# combo.net
KiCad netlist of a schematic drawn in EAGLE
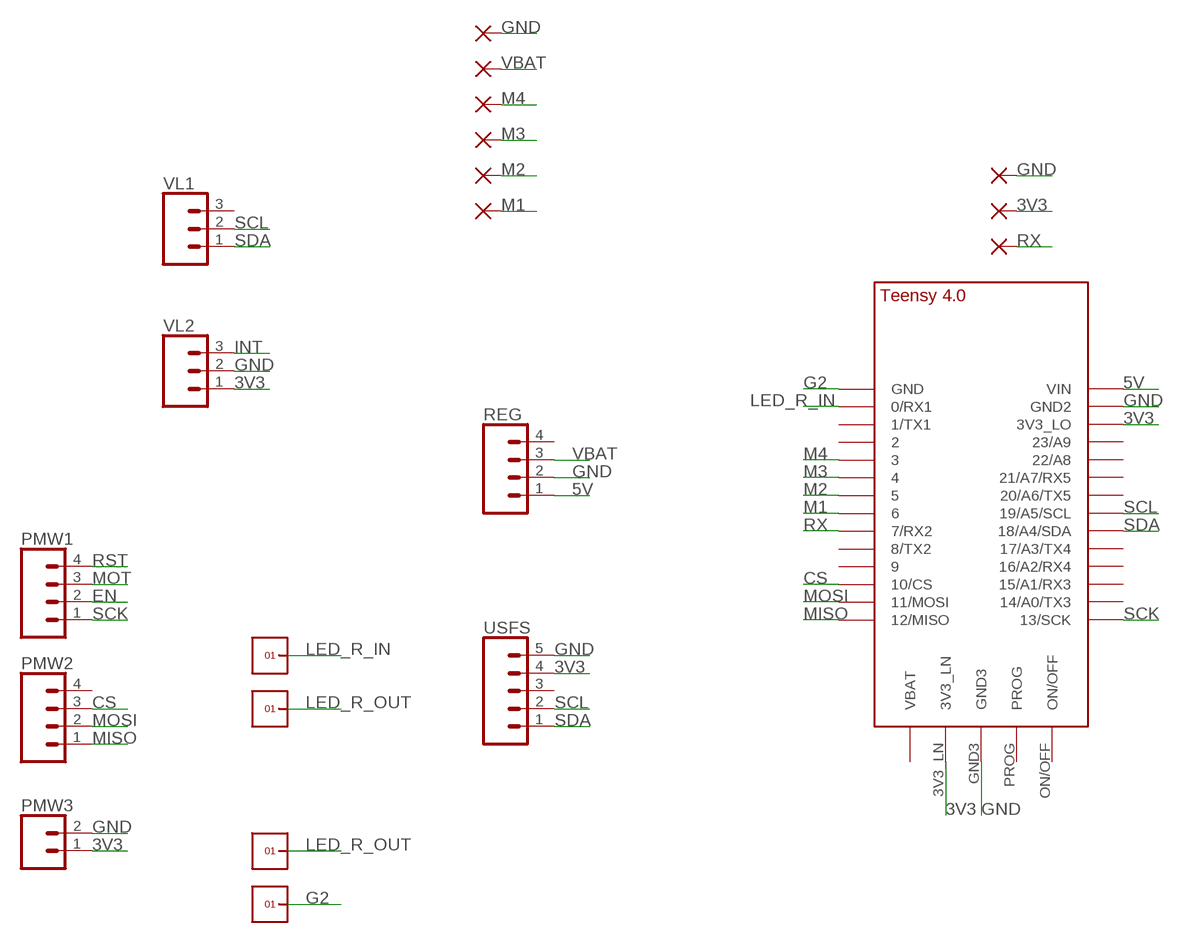
[diagram p0: schematic, sheet 1]

(export (version "E")
  (design (tool "Eeschema 10.0.6"))
  (components
    (comp (ref "3V")
      (value "SMD2")
      (footprint "eagle-import:SMD1,27-2,54")
      (libsource (lib "eagle-import") (part "SMD2"))
    )
    (comp (ref "GD")
      (value "SMD2")
      (footprint "eagle-import:SMD1,27-2,54")
      (libsource (lib "eagle-import") (part "SMD2"))
    )
    (comp (ref "GND")
      (value "SMD2")
      (footprint "eagle-import:SMD1,27-2,54")
      (libsource (lib "eagle-import") (part "SMD2"))
    )
    (comp (ref "M1")
      (value "SMD2")
      (footprint "eagle-import:SMD1,27-2,54")
      (libsource (lib "eagle-import") (part "SMD2"))
    )
    (comp (ref "M2")
      (value "SMD2")
      (footprint "eagle-import:SMD1,27-2,54")
      (libsource (lib "eagle-import") (part "SMD2"))
    )
    (comp (ref "M3")
      (value "SMD2")
      (footprint "eagle-import:SMD1,27-2,54")
      (libsource (lib "eagle-import") (part "SMD2"))
    )
    (comp (ref "M4")
      (value "SMD2")
      (footprint "eagle-import:SMD1,27-2,54")
      (libsource (lib "eagle-import") (part "SMD2"))
    )
    (comp (ref "PMW1")
      (value "CONN_041X04_NO_SILK")
      (footprint "eagle-import:1X04_NO_SILK")
      (libsource (lib "eagle-import") (part "CONN_041X04_NO_SILK"))
    )
    (comp (ref "PMW2")
      (value "CONN_041X04_NO_SILK")
      (footprint "eagle-import:1X04_NO_SILK")
      (libsource (lib "eagle-import") (part "CONN_041X04_NO_SILK"))
    )
    (comp (ref "PMW3")
      (value "CONN_021X02_NO_SILK")
      (footprint "eagle-import:1X02_NO_SILK")
      (libsource (lib "eagle-import") (part "CONN_021X02_NO_SILK"))
    )
    (comp (ref "REG")
      (value "CONN_041X04_NO_SILK")
      (footprint "eagle-import:1X04_NO_SILK")
      (libsource (lib "eagle-import") (part "CONN_041X04_NO_SILK"))
    )
    (comp (ref "RX")
      (value "SMD2")
      (footprint "eagle-import:SMD1,27-2,54")
      (libsource (lib "eagle-import") (part "SMD2"))
    )
    (comp (ref "U$1")
      (value "TEENSY_4.0")
      (footprint "eagle-import:TEENSY_4.0")
      (libsource (lib "eagle-import") (part "TEENSY_4.0"))
    )
    (comp (ref "U$3")
      (value "1X1")
      (footprint "eagle-import:1X1")
      (libsource (lib "eagle-import") (part "1X1"))
    )
    (comp (ref "U$4")
      (value "1X1")
      (footprint "eagle-import:1X1")
      (libsource (lib "eagle-import") (part "1X1"))
    )
    (comp (ref "U$6")
      (value "1X1")
      (footprint "eagle-import:1X1")
      (libsource (lib "eagle-import") (part "1X1"))
    )
    (comp (ref "U$7")
      (value "1X1")
      (footprint "eagle-import:1X1")
      (libsource (lib "eagle-import") (part "1X1"))
    )
    (comp (ref "USFS")
      (value "CONN_05NO_SILK")
      (footprint "eagle-import:1X05_NO_SILK")
      (libsource (lib "eagle-import") (part "CONN_05NO_SILK"))
    )
    (comp (ref "VBAT")
      (value "SMD2")
      (footprint "eagle-import:SMD1,27-2,54")
      (libsource (lib "eagle-import") (part "SMD2"))
    )
    (comp (ref "VL1")
      (value "CONN_031X03_NO_SILK")
      (footprint "eagle-import:1X03_NO_SILK")
      (libsource (lib "eagle-import") (part "CONN_031X03_NO_SILK"))
    )
    (comp (ref "VL2")
      (value "CONN_031X03_NO_SILK")
      (footprint "eagle-import:1X03_NO_SILK")
      (libsource (lib "eagle-import") (part "CONN_031X03_NO_SILK"))
    )
  )
  (nets
    (net (code "1") (name "/3V3") (class "Default")
      (node (ref "3V") (pin "1") (pinfunction "P_1") (pintype "passive"))
      (node (ref "PMW3") (pin "1") (pinfunction "1_1") (pintype "passive"))
      (node (ref "U$1") (pin "3V3_LN") (pinfunction "3V3_LN_3V3_LN") (pintype "bidirectional"))
      (node (ref "U$1") (pin "3V3_LO") (pinfunction "3V3_LO_3V3_LO") (pintype "bidirectional"))
      (node (ref "USFS") (pin "4") (pinfunction "4_4") (pintype "passive"))
      (node (ref "VL2") (pin "1") (pinfunction "1_1") (pintype "passive"))
    )
    (net (code "2") (name "/5V") (class "Default")
      (node (ref "REG") (pin "1") (pinfunction "1_1") (pintype "passive"))
      (node (ref "U$1") (pin "VIN") (pinfunction "VIN_VIN") (pintype "bidirectional"))
    )
    (net (code "3") (name "/CS") (class "Default")
      (node (ref "PMW2") (pin "3") (pinfunction "3_3") (pintype "passive"))
      (node (ref "U$1") (pin "10/CS") (pinfunction "10/CS_10/CS") (pintype "bidirectional"))
    )
    (net (code "4") (name "/EN") (class "Default")
      (node (ref "PMW1") (pin "2") (pinfunction "2_2") (pintype "passive"))
    )
    (net (code "5") (name "/G2") (class "Default")
      (node (ref "U$1") (pin "GND") (pinfunction "GND_GND") (pintype "bidirectional"))
      (node (ref "U$7") (pin "1") (pinfunction "1_1") (pintype "bidirectional"))
    )
    (net (code "6") (name "/GND") (class "Default")
      (node (ref "GD") (pin "1") (pinfunction "P_1") (pintype "passive"))
      (node (ref "GND") (pin "1") (pinfunction "P_1") (pintype "passive"))
      (node (ref "PMW3") (pin "2") (pinfunction "2_2") (pintype "passive"))
      (node (ref "REG") (pin "2") (pinfunction "2_2") (pintype "passive"))
      (node (ref "U$1") (pin "GND2") (pinfunction "GND2_GND2") (pintype "bidirectional"))
      (node (ref "U$1") (pin "GND3") (pinfunction "GND3_GND3") (pintype "bidirectional"))
      (node (ref "USFS") (pin "5") (pinfunction "5_5") (pintype "passive"))
      (node (ref "VL2") (pin "2") (pinfunction "2_2") (pintype "passive"))
    )
    (net (code "7") (name "/INT") (class "Default")
      (node (ref "VL2") (pin "3") (pinfunction "3_3") (pintype "passive"))
    )
    (net (code "8") (name "/LED_R_IN") (class "Default")
      (node (ref "U$1") (pin "0/RX") (pinfunction "0/RX1_0/RX") (pintype "bidirectional"))
      (node (ref "U$3") (pin "1") (pinfunction "1_1") (pintype "bidirectional"))
    )
    (net (code "9") (name "/LED_R_OUT") (class "Default")
      (node (ref "U$4") (pin "1") (pinfunction "1_1") (pintype "bidirectional"))
      (node (ref "U$6") (pin "1") (pinfunction "1_1") (pintype "bidirectional"))
    )
    (net (code "10") (name "/M1") (class "Default")
      (node (ref "M1") (pin "1") (pinfunction "P_1") (pintype "passive"))
      (node (ref "U$1") (pin "6") (pinfunction "6_6") (pintype "bidirectional"))
    )
    (net (code "11") (name "/M2") (class "Default")
      (node (ref "M2") (pin "1") (pinfunction "P_1") (pintype "passive"))
      (node (ref "U$1") (pin "5") (pinfunction "5_5") (pintype "bidirectional"))
    )
    (net (code "12") (name "/M3") (class "Default")
      (node (ref "M3") (pin "1") (pinfunction "P_1") (pintype "passive"))
      (node (ref "U$1") (pin "4/CANRX") (pinfunction "4_4/CANRX") (pintype "bidirectional"))
    )
    (net (code "13") (name "/M4") (class "Default")
      (node (ref "M4") (pin "1") (pinfunction "P_1") (pintype "passive"))
      (node (ref "U$1") (pin "3/CANTX") (pinfunction "3_3/CANTX") (pintype "bidirectional"))
    )
    (net (code "14") (name "/MISO") (class "Default")
      (node (ref "PMW2") (pin "1") (pinfunction "1_1") (pintype "passive"))
      (node (ref "U$1") (pin "12/MISO") (pinfunction "12/MISO_12/MISO") (pintype "bidirectional"))
    )
    (net (code "15") (name "/MOSI") (class "Default")
      (node (ref "PMW2") (pin "2") (pinfunction "2_2") (pintype "passive"))
      (node (ref "U$1") (pin "11/MOSI") (pinfunction "11/MOSI_11/MOSI") (pintype "bidirectional"))
    )
    (net (code "16") (name "/MOT") (class "Default")
      (node (ref "PMW1") (pin "3") (pinfunction "3_3") (pintype "passive"))
    )
    (net (code "17") (name "/RST") (class "Default")
      (node (ref "PMW1") (pin "4") (pinfunction "4_4") (pintype "passive"))
    )
    (net (code "18") (name "/RX") (class "Default")
      (node (ref "RX") (pin "1") (pinfunction "P_1") (pintype "passive"))
      (node (ref "U$1") (pin "7") (pinfunction "7/RX2_7") (pintype "bidirectional"))
    )
    (net (code "19") (name "/SCK") (class "Default")
      (node (ref "PMW1") (pin "1") (pinfunction "1_1") (pintype "passive"))
      (node (ref "U$1") (pin "13/SCK") (pinfunction "13/SCK_13/SCK") (pintype "bidirectional"))
    )
    (net (code "20") (name "/SCL") (class "Default")
      (node (ref "U$1") (pin "19/A5/SCL") (pinfunction "19/A5/SCL_19/A5/SCL") (pintype "bidirectional"))
      (node (ref "USFS") (pin "2") (pinfunction "2_2") (pintype "passive"))
      (node (ref "VL1") (pin "2") (pinfunction "2_2") (pintype "passive"))
    )
    (net (code "21") (name "/SDA") (class "Default")
      (node (ref "U$1") (pin "18/A4/SDA") (pinfunction "18/A4/SDA_18/A4/SDA") (pintype "bidirectional"))
      (node (ref "USFS") (pin "1") (pinfunction "1_1") (pintype "passive"))
      (node (ref "VL1") (pin "1") (pinfunction "1_1") (pintype "passive"))
    )
    (net (code "22") (name "/VBAT") (class "Default")
      (node (ref "REG") (pin "3") (pinfunction "3_3") (pintype "passive"))
      (node (ref "VBAT") (pin "1") (pinfunction "P_1") (pintype "passive"))
    )
    (net (code "23") (name "unconnected-(PMW2-Pad4)") (class "Default")
      (node (ref "PMW2") (pin "4") (pinfunction "4_4") (pintype "passive"))
    )
    (net (code "24") (name "unconnected-(REG-Pad4)") (class "Default")
      (node (ref "REG") (pin "4") (pinfunction "4_4") (pintype "passive"))
    )
    (net (code "25") (name "unconnected-(U$1-1{slash}TX1-Pad1{slash}TX)") (class "Default")
      (node (ref "U$1") (pin "1/TX") (pinfunction "1/TX1_1/TX") (pintype "bidirectional"))
    )
    (net (code "26") (name "unconnected-(U$1-8{slash}TX2-Pad8)") (class "Default")
      (node (ref "U$1") (pin "8") (pinfunction "8/TX2_8") (pintype "bidirectional"))
    )
    (net (code "27") (name "unconnected-(U$1-9-Pad9{slash}CS)") (class "Default")
      (node (ref "U$1") (pin "9/CS") (pinfunction "9_9/CS") (pintype "bidirectional"))
    )
    (net (code "28") (name "unconnected-(U$1-14{slash}A0{slash}TX3-Pad14{slash}A0)") (class "Default")
      (node (ref "U$1") (pin "14/A0") (pinfunction "14/A0/TX3_14/A0") (pintype "bidirectional"))
    )
    (net (code "29") (name "unconnected-(U$1-15{slash}A1{slash}RX3-Pad15{slash}A1)") (class "Default")
      (node (ref "U$1") (pin "15/A1") (pinfunction "15/A1/RX3_15/A1") (pintype "bidirectional"))
    )
    (net (code "30") (name "unconnected-(U$1-16{slash}A2{slash}RX4-Pad16{slash}A2)") (class "Default")
      (node (ref "U$1") (pin "16/A2") (pinfunction "16/A2/RX4_16/A2") (pintype "bidirectional"))
    )
    (net (code "31") (name "unconnected-(U$1-17{slash}A3{slash}TX4-Pad17{slash}A3)") (class "Default")
      (node (ref "U$1") (pin "17/A3") (pinfunction "17/A3/TX4_17/A3") (pintype "bidirectional"))
    )
    (net (code "32") (name "unconnected-(U$1-20{slash}A6{slash}TX5-Pad20{slash}A6)") (class "Default")
      (node (ref "U$1") (pin "20/A6") (pinfunction "20/A6/TX5_20/A6") (pintype "bidirectional"))
    )
    (net (code "33") (name "unconnected-(U$1-21{slash}A7{slash}RX5-Pad21{slash}A7)") (class "Default")
      (node (ref "U$1") (pin "21/A7") (pinfunction "21/A7/RX5_21/A7") (pintype "bidirectional"))
    )
    (net (code "34") (name "unconnected-(U$1-Pad2)") (class "Default")
      (node (ref "U$1") (pin "2") (pinfunction "2_2") (pintype "bidirectional"))
    )
    (net (code "35") (name "unconnected-(U$1-Pad22{slash}A8)") (class "Default")
      (node (ref "U$1") (pin "22/A8") (pinfunction "22/A8_22/A8") (pintype "bidirectional"))
    )
    (net (code "36") (name "unconnected-(U$1-Pad23{slash}A9)") (class "Default")
      (node (ref "U$1") (pin "23/A9") (pinfunction "23/A9_23/A9") (pintype "bidirectional"))
    )
    (net (code "37") (name "unconnected-(U$1-PadON{slash}OFF)") (class "Default")
      (node (ref "U$1") (pin "ON/OFF") (pinfunction "ON/OFF_ON/OFF") (pintype "bidirectional"))
    )
    (net (code "38") (name "unconnected-(U$1-PadPROG)") (class "Default")
      (node (ref "U$1") (pin "PROG") (pinfunction "PROG_PROG") (pintype "bidirectional"))
    )
    (net (code "39") (name "unconnected-(U$1-VBAT-PadVBAT\\)") (class "Default")
      (node (ref "U$1") (pin "VBAT\\") (pinfunction "VBAT_VBAT\\") (pintype "bidirectional"))
    )
    (net (code "40") (name "unconnected-(USFS-Pad3)") (class "Default")
      (node (ref "USFS") (pin "3") (pinfunction "3_3") (pintype "passive"))
    )
    (net (code "41") (name "unconnected-(VL1-Pad3)") (class "Default")
      (node (ref "VL1") (pin "3") (pinfunction "3_3") (pintype "passive"))
    )
  )
)
